# ESP32Design.net
KiCad netlist of a schematic drawn in Altium Designer
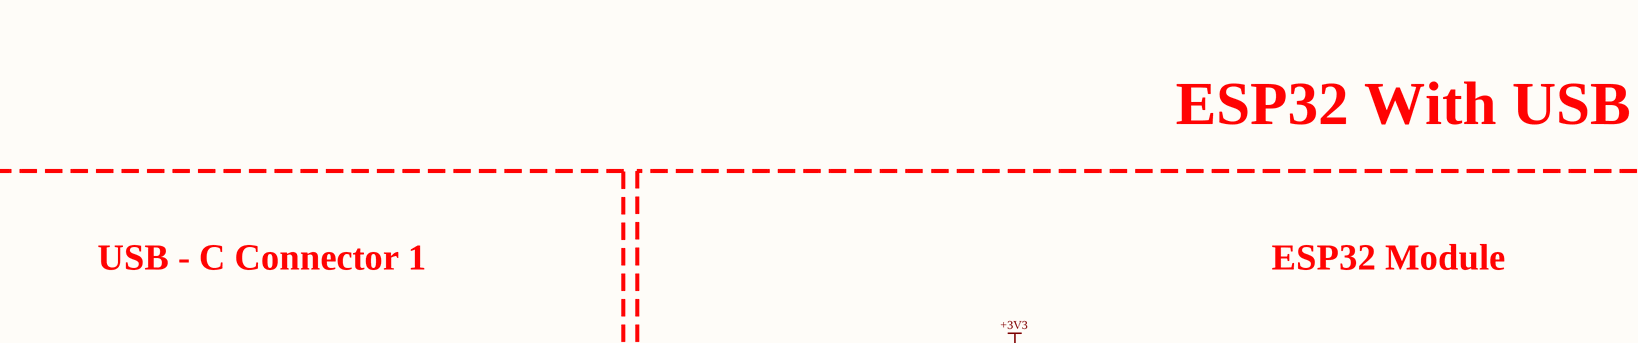
[diagram p0: ESP32Design.SchDoc, top left]
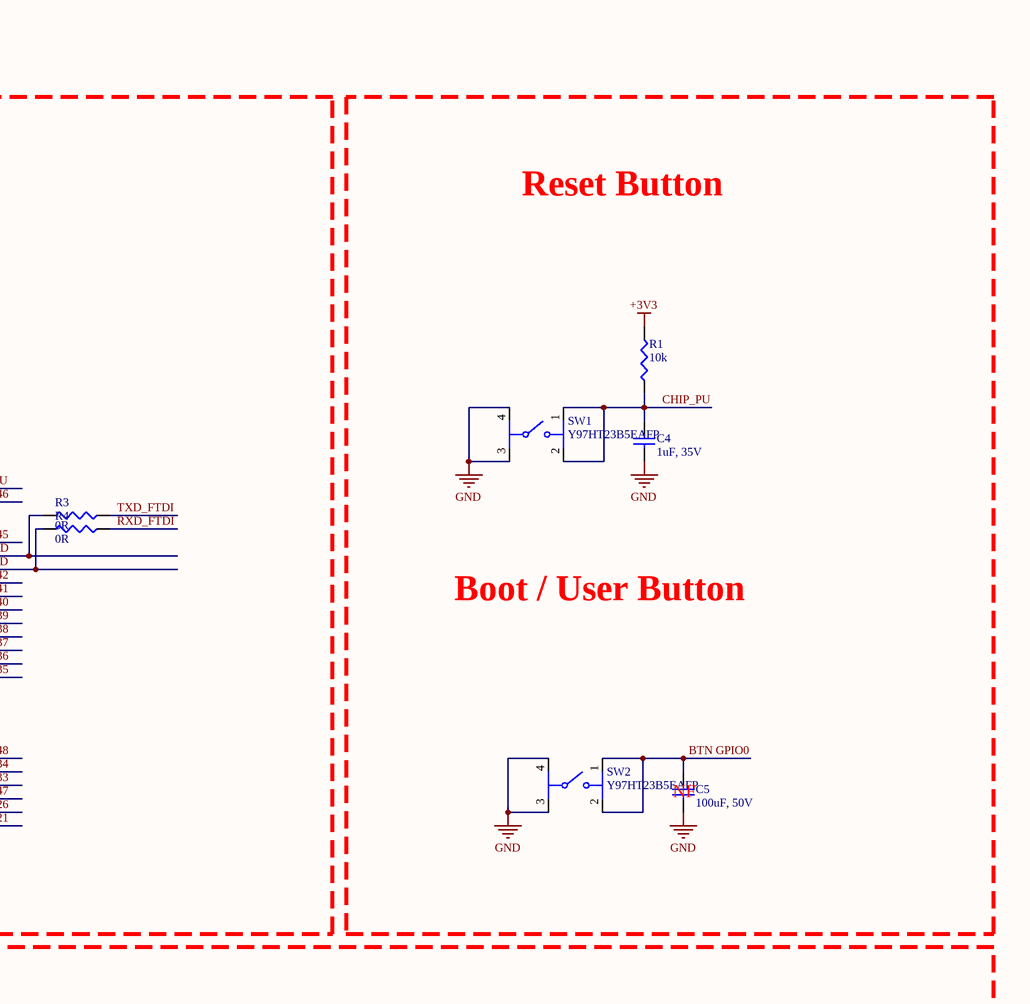
[diagram p1: ESP32Design.SchDoc, top right]
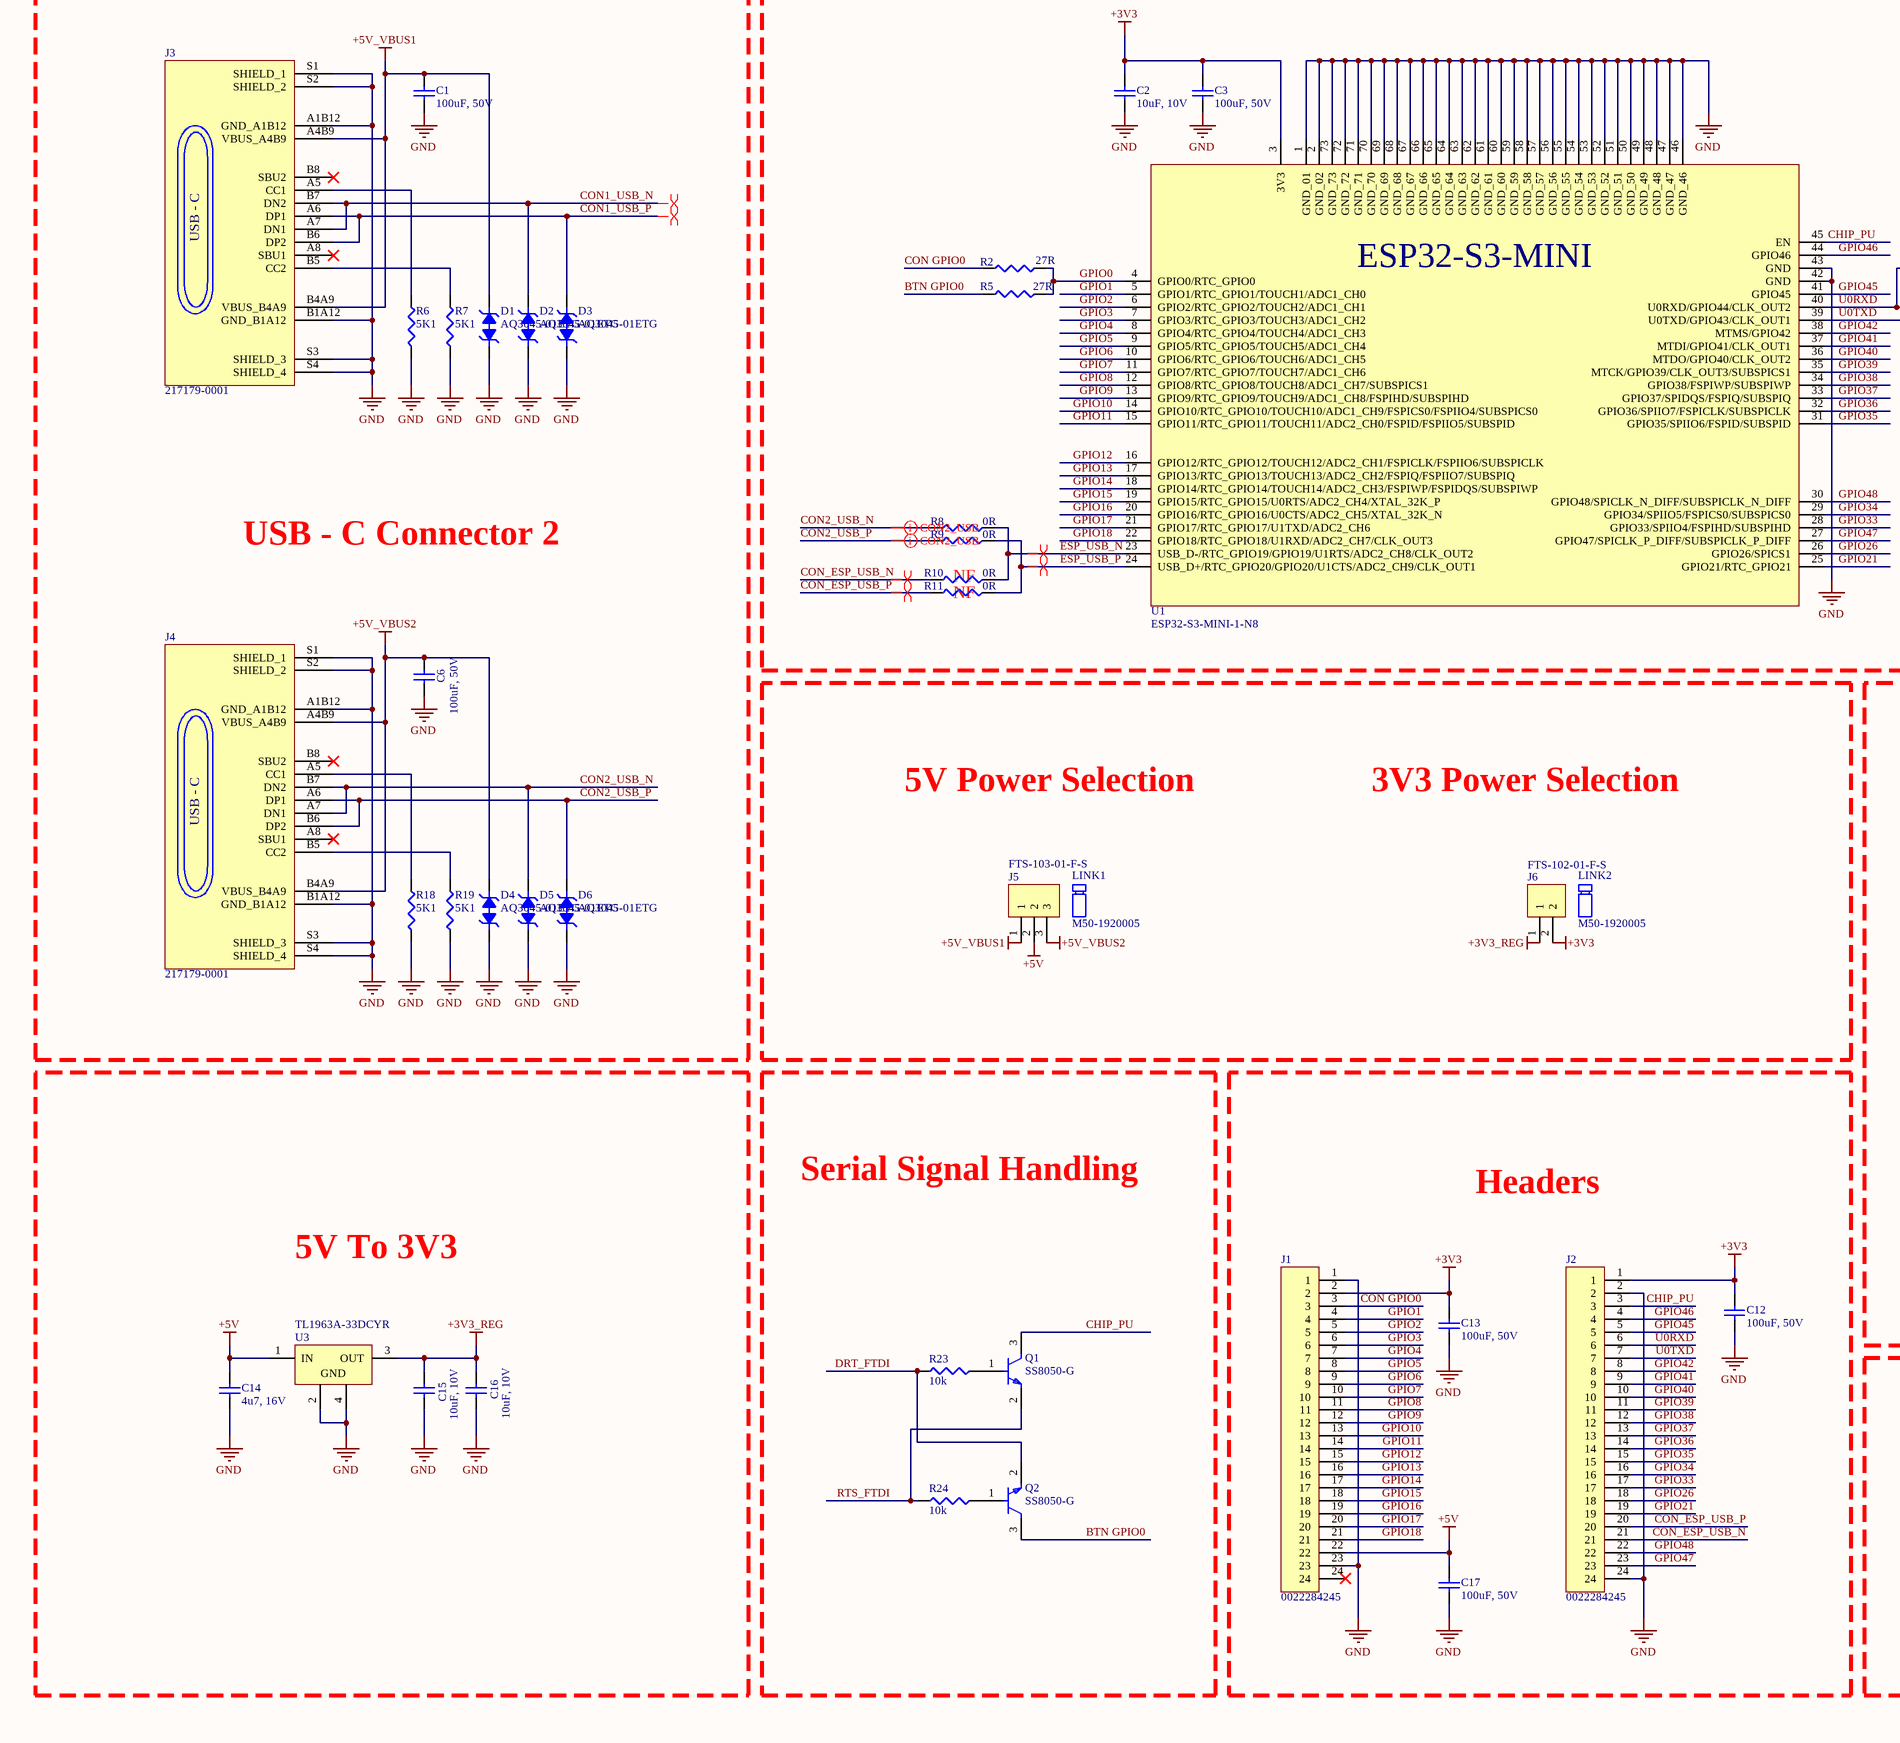
[diagram p2: ESP32Design.SchDoc, bottom left]
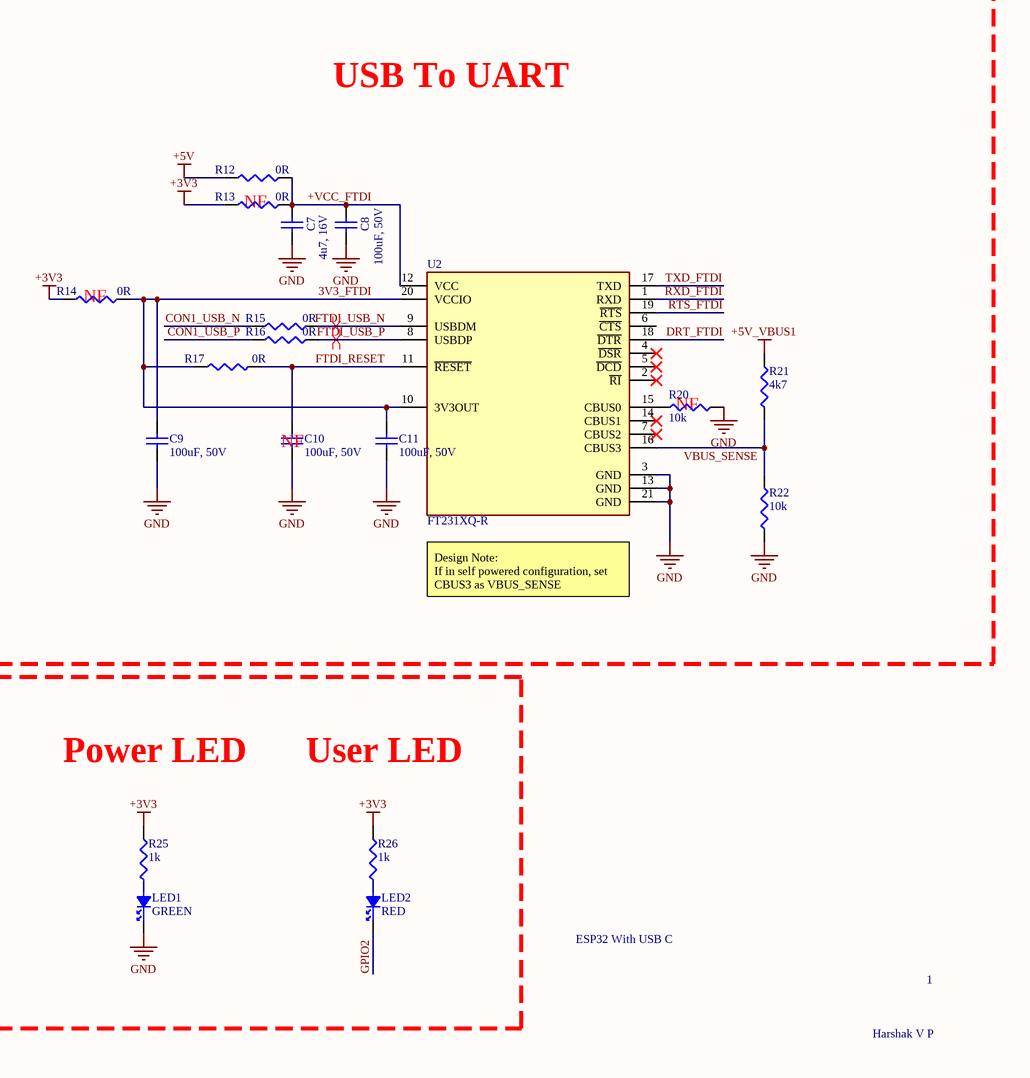
[diagram p3: ESP32Design.SchDoc, bottom right]

(export (version "E")
  (design (tool "Eeschema 10.0.6"))
  (components
    (comp (ref "C1")
      (value "100uF, 50V")
      (footprint "CAPC1005X65N")
      (description "CAP CER 0.1UF 50V X7R 0402")
      (fields
        (field (name "MANUFACTURER") "Samsung Electro-Mechanics")
        (field (name "MANUFACTURER PART NUMBER") "CL05B104KB54PNC")
      )
      (libsource (lib "SchLib") (part "CL05B104KB54PNC"))
    )
    (comp (ref "C2")
      (value "10uF, 10V")
      (footprint "CAPC1005X65N")
      (description "CAP CER 10UF 10V X5R 0402")
      (fields
        (field (name "MANUFACTURER") "Samsung Electro-Mechanics")
        (field (name "MANUFACTURER PART NUMBER") "CL05A106MP8NUB8")
      )
      (libsource (lib "SchLib") (part "CL05A106MP8NUB8"))
    )
    (comp (ref "C3")
      (value "100uF, 50V")
      (footprint "CAPC1005X65N")
      (description "CAP CER 0.1UF 50V X7R 0402")
      (fields
        (field (name "MANUFACTURER") "Samsung Electro-Mechanics")
        (field (name "MANUFACTURER PART NUMBER") "CL05B104KB54PNC")
      )
      (libsource (lib "SchLib") (part "CL05B104KB54PNC"))
    )
    (comp (ref "C4")
      (value "1uF, 35V")
      (footprint "CAPC1005X65N")
      (description "CAP CER 1UF 35V X5R 0402")
      (fields
        (field (name "MANUFACTURER") "Samsung Electro-Mechanics")
        (field (name "MANUFACTURER PART NUMBER") "CL05A105KL5NRNC")
      )
      (libsource (lib "SchLib") (part "CL05A105KL5NRNC"))
    )
    (comp (ref "C5")
      (value "100uF, 50V")
      (footprint "CAPC1005X65N")
      (description "CAP CER 0.1UF 50V X7R 0402")
      (fields
        (field (name "MANUFACTURER") "Samsung Electro-Mechanics")
        (field (name "MANUFACTURER PART NUMBER") "CL05B104KB54PNC")
      )
      (libsource (lib "SchLib") (part "CL05B104KB54PNC"))
    )
    (comp (ref "C6")
      (value "100uF, 50V")
      (footprint "CAPC1005X65N")
      (description "CAP CER 0.1UF 50V X7R 0402")
      (fields
        (field (name "MANUFACTURER") "Samsung Electro-Mechanics")
        (field (name "MANUFACTURER PART NUMBER") "CL05B104KB54PNC")
      )
      (libsource (lib "SchLib") (part "CL05B104KB54PNC"))
    )
    (comp (ref "C7")
      (value "4u7, 16V")
      (footprint "CAPC1005X65N")
      (description "CAP CER 4.7UF 16V X5R 0402")
      (fields
        (field (name "MANUFACTURER") "Samsung Electro-Mechanics")
        (field (name "MANUFACTURER PART NUMBER") "CL05A475MO5NUNC")
      )
      (libsource (lib "SchLib") (part "CL05A475MO5NUNC"))
    )
    (comp (ref "C8")
      (value "100uF, 50V")
      (footprint "CAPC1005X65N")
      (description "CAP CER 0.1UF 50V X7R 0402")
      (fields
        (field (name "MANUFACTURER") "Samsung Electro-Mechanics")
        (field (name "MANUFACTURER PART NUMBER") "CL05B104KB54PNC")
      )
      (libsource (lib "SchLib") (part "CL05B104KB54PNC"))
    )
    (comp (ref "C9")
      (value "100uF, 50V")
      (footprint "CAPC1005X65N")
      (description "CAP CER 0.1UF 50V X7R 0402")
      (fields
        (field (name "MANUFACTURER") "Samsung Electro-Mechanics")
        (field (name "MANUFACTURER PART NUMBER") "CL05B104KB54PNC")
      )
      (libsource (lib "SchLib") (part "CL05B104KB54PNC"))
    )
    (comp (ref "C10")
      (value "100uF, 50V")
      (footprint "CAPC1005X65N")
      (description "CAP CER 0.1UF 50V X7R 0402")
      (fields
        (field (name "MANUFACTURER") "Samsung Electro-Mechanics")
        (field (name "MANUFACTURER PART NUMBER") "CL05B104KB54PNC")
      )
      (libsource (lib "SchLib") (part "CL05B104KB54PNC"))
    )
    (comp (ref "C11")
      (value "100uF, 50V")
      (footprint "CAPC1005X65N")
      (description "CAP CER 0.1UF 50V X7R 0402")
      (fields
        (field (name "MANUFACTURER") "Samsung Electro-Mechanics")
        (field (name "MANUFACTURER PART NUMBER") "CL05B104KB54PNC")
      )
      (libsource (lib "SchLib") (part "CL05B104KB54PNC"))
    )
    (comp (ref "C12")
      (value "100uF, 50V")
      (footprint "CAPC1005X65N")
      (description "CAP CER 0.1UF 50V X7R 0402")
      (fields
        (field (name "MANUFACTURER") "Samsung Electro-Mechanics")
        (field (name "MANUFACTURER PART NUMBER") "CL05B104KB54PNC")
      )
      (libsource (lib "SchLib") (part "CL05B104KB54PNC"))
    )
    (comp (ref "C13")
      (value "100uF, 50V")
      (footprint "CAPC1005X65N")
      (description "CAP CER 0.1UF 50V X7R 0402")
      (fields
        (field (name "MANUFACTURER") "Samsung Electro-Mechanics")
        (field (name "MANUFACTURER PART NUMBER") "CL05B104KB54PNC")
      )
      (libsource (lib "SchLib") (part "CL05B104KB54PNC"))
    )
    (comp (ref "C14")
      (value "4u7, 16V")
      (footprint "CAPC1005X65N")
      (description "CAP CER 4.7UF 16V X5R 0402")
      (fields
        (field (name "MANUFACTURER") "Samsung Electro-Mechanics")
        (field (name "MANUFACTURER PART NUMBER") "CL05A475MO5NUNC")
      )
      (libsource (lib "SchLib") (part "CL05A475MO5NUNC"))
    )
    (comp (ref "C15")
      (value "10uF, 10V")
      (footprint "CAPC1005X65N")
      (description "CAP CER 10UF 10V X5R 0402")
      (fields
        (field (name "MANUFACTURER") "Samsung Electro-Mechanics")
        (field (name "MANUFACTURER PART NUMBER") "CL05A106MP8NUB8")
      )
      (libsource (lib "SchLib") (part "CL05A106MP8NUB8"))
    )
    (comp (ref "C16")
      (value "10uF, 10V")
      (footprint "CAPC1005X65N")
      (description "CAP CER 10UF 10V X5R 0402")
      (fields
        (field (name "MANUFACTURER") "Samsung Electro-Mechanics")
        (field (name "MANUFACTURER PART NUMBER") "CL05A106MP8NUB8")
      )
      (libsource (lib "SchLib") (part "CL05A106MP8NUB8"))
    )
    (comp (ref "C17")
      (value "100uF, 50V")
      (footprint "CAPC1005X65N")
      (description "CAP CER 0.1UF 50V X7R 0402")
      (fields
        (field (name "MANUFACTURER") "Samsung Electro-Mechanics")
        (field (name "MANUFACTURER PART NUMBER") "CL05B104KB54PNC")
      )
      (libsource (lib "SchLib") (part "CL05B104KB54PNC"))
    )
    (comp (ref "D1")
      (value "AQ3045-01ETG")
      (footprint "SOD882")
      (description "TVS DIODE 5.3VWM 12VC SOD882")
      (fields (field (name "MANUFACTURER") "Littelfuse") (field (name "LCS PART NUMBER") "C3710326"))
      (libsource (lib "SchLib") (part "AQ3045-01ETG"))
    )
    (comp (ref "D2")
      (value "AQ3045-01ETG")
      (footprint "SOD882")
      (description "TVS DIODE 5.3VWM 12VC SOD882")
      (fields (field (name "MANUFACTURER") "Littelfuse") (field (name "LCS PART NUMBER") "C3710326"))
      (libsource (lib "SchLib") (part "AQ3045-01ETG"))
    )
    (comp (ref "D3")
      (value "AQ3045-01ETG")
      (footprint "SOD882")
      (description "TVS DIODE 5.3VWM 12VC SOD882")
      (fields (field (name "MANUFACTURER") "Littelfuse") (field (name "LCS PART NUMBER") "C3710326"))
      (libsource (lib "SchLib") (part "AQ3045-01ETG"))
    )
    (comp (ref "D4")
      (value "AQ3045-01ETG")
      (footprint "SOD882")
      (description "TVS DIODE 5.3VWM 12VC SOD882")
      (fields (field (name "MANUFACTURER") "Littelfuse") (field (name "LCS PART NUMBER") "C3710326"))
      (libsource (lib "SchLib") (part "AQ3045-01ETG"))
    )
    (comp (ref "D5")
      (value "AQ3045-01ETG")
      (footprint "SOD882")
      (description "TVS DIODE 5.3VWM 12VC SOD882")
      (fields (field (name "MANUFACTURER") "Littelfuse") (field (name "LCS PART NUMBER") "C3710326"))
      (libsource (lib "SchLib") (part "AQ3045-01ETG"))
    )
    (comp (ref "D6")
      (value "AQ3045-01ETG")
      (footprint "SOD882")
      (description "TVS DIODE 5.3VWM 12VC SOD882")
      (fields (field (name "MANUFACTURER") "Littelfuse") (field (name "LCS PART NUMBER") "C3710326"))
      (libsource (lib "SchLib") (part "AQ3045-01ETG"))
    )
    (comp (ref "J1")
      (value "0022284245")
      (footprint "HDR_1X24_2.54MM")
      (description "CONN HEADER VERT 24POS 2.54MM")
      (fields (field (name "MANUFACTURER") "Molex") (field (name "MANUFACTURER PART NUMBER") "22-28-4245"))
      (libsource (lib "SchLib") (part "0022284245"))
    )
    (comp (ref "J2")
      (value "0022284245")
      (footprint "HDR_1X24_2.54MM")
      (description "CONN HEADER VERT 24POS 2.54MM")
      (fields (field (name "MANUFACTURER") "Molex") (field (name "MANUFACTURER PART NUMBER") "22-28-4245"))
      (libsource (lib "SchLib") (part "0022284245"))
    )
    (comp (ref "J3")
      (value "217179-0001")
      (footprint "FP-2171790001-MFG")
      (description "CONN RCP USB2.0 TYP C 24P SMD RA")
      (fields (field (name "MANUFACTURER") "Molex") (field (name "LCSC PART NUMBER") "C3197684"))
      (libsource (lib "SchLib") (part "217179-0001"))
    )
    (comp (ref "J4")
      (value "217179-0001")
      (footprint "FP-2171790001-MFG")
      (description "CONN RCP USB2.0 TYP C 24P SMD RA")
      (fields (field (name "MANUFACTURER") "Molex") (field (name "LCSC PART NUMBER") "C3197684"))
      (libsource (lib "SchLib") (part "217179-0001"))
    )
    (comp (ref "J5")
      (value "FTS-103-01-F-S")
      (footprint "HDR_1X3_1.27MM")
      (description "CONN HEADER VERT 3POS 1.27MM")
      (fields (field (name "MANUFACTURER") "Samtec") (field (name "LCSC PART NUMBER") "C3333578"))
      (libsource (lib "SchLib") (part "FTS-103-01-F-S"))
    )
    (comp (ref "J6")
      (value "FTS-102-01-F-S")
      (footprint "HDR_1X2_1.27MM")
      (description "CONN HEADER VERT 2POS 1.27MM")
      (fields (field (name "MANUFACTURER") "Samtec"))
      (libsource (lib "SchLib") (part "FTS-102-01-F-S"))
    )
    (comp (ref "LED1")
      (value "GREEN")
      (footprint "LED0402G")
      (description "LED GREEN 0402 SMD")
      (fields
        (field (name "MANUFACTURER") "Vishay")
        (field (name "MANUFACTURER PART NUMBER") "VLMTG1500-GS08")
      )
      (libsource (lib "SchLib") (part "VLMTG1500-GS08"))
    )
    (comp (ref "LED2")
      (value "RED")
      (footprint "LED0402R")
      (description "CHIPLED(0402) SUPER RED ULTRABRI")
      (fields
        (field (name "MANUFACTURER") "Vishay")
        (field (name "MANUFACTURER PART NUMBER") "VLMS1502-GS08")
      )
      (libsource (lib "SchLib") (part "VLMS1502-GS08"))
    )
    (comp (ref "LINK1")
      (value "M50-1920005")
      (description "CONN SHUNT 1.27MM RED")
      (fields (field (name "MANUFACTURER") "Harwin"))
      (libsource (lib "SchLib") (part "M50-1920005"))
    )
    (comp (ref "LINK2")
      (value "M50-1920005")
      (description "CONN SHUNT 1.27MM RED")
      (fields (field (name "MANUFACTURER") "Harwin"))
      (libsource (lib "SchLib") (part "M50-1920005"))
    )
    (comp (ref "Q1")
      (value "SS8050-G")
      (footprint "FP-SS8050-G-IPC_B")
      (description "TRANS NPN 25V 1.5A SOT-23-3")
      (fields (field (name "MANUFACTURER") "Comchip"))
      (libsource (lib "SchLib") (part "SS8050-G"))
    )
    (comp (ref "Q2")
      (value "SS8050-G")
      (footprint "FP-SS8050-G-IPC_B")
      (description "TRANS NPN 25V 1.5A SOT-23-3")
      (fields (field (name "MANUFACTURER") "Comchip"))
      (libsource (lib "SchLib") (part "SS8050-G"))
    )
    (comp (ref "R1")
      (value "10k")
      (footprint "RESC1005X37N")
      (description "RES SMD 10K OHM 1% 1/16W 0402")
      (fields
        (field (name "MANUFACTURER") "Yageo Group")
        (field (name "MANUFACTURER PART NUMBER") "AC0402FR-0710KL")
      )
      (libsource (lib "SchLib") (part "AC0402FR-0710KL"))
    )
    (comp (ref "R2")
      (value "27R")
      (footprint "RESC1005X37N")
      (description "RES 27 OHM 1% 1/16W 0402")
      (fields
        (field (name "MANUFACTURER") "Yageo Group")
        (field (name "MANUFACTURER PART NUMBER") "RC0402FR-0727RL")
      )
      (libsource (lib "SchLib") (part "RC0402FR-0727RL"))
    )
    (comp (ref "R3")
      (value "0R")
      (footprint "RESC1005X37N")
      (description "RES 0 OHM JUMPER 1/16W 0402")
      (fields
        (field (name "MANUFACTURER") "Yageo Group")
        (field (name "MANUFACTURER PART NUMBER") "RC0402JR-070RL")
      )
      (libsource (lib "SchLib") (part "RC0402JR-070RL"))
    )
    (comp (ref "R4")
      (value "0R")
      (footprint "RESC1005X37N")
      (description "RES 0 OHM JUMPER 1/16W 0402")
      (fields
        (field (name "MANUFACTURER") "Yageo Group")
        (field (name "MANUFACTURER PART NUMBER") "RC0402JR-070RL")
      )
      (libsource (lib "SchLib") (part "RC0402JR-070RL"))
    )
    (comp (ref "R5")
      (value "27R")
      (footprint "RESC1005X37N")
      (description "RES 27 OHM 1% 1/16W 0402")
      (fields
        (field (name "MANUFACTURER") "Yageo Group")
        (field (name "MANUFACTURER PART NUMBER") "RC0402FR-0727RL")
      )
      (libsource (lib "SchLib") (part "RC0402FR-0727RL"))
    )
    (comp (ref "R6")
      (value "5K1")
      (footprint "RESC1005X37N")
      (description "RES SMD 5.1K OHM 1% 1/16W 0402")
      (fields
        (field (name "MANUFACTURER") "Yageo Group")
        (field (name "MANUFACTURER PART NUMBER") "AC0402FR-075K1L")
      )
      (libsource (lib "SchLib") (part "AC0402FR-075K1L"))
    )
    (comp (ref "R7")
      (value "5K1")
      (footprint "RESC1005X37N")
      (description "RES SMD 5.1K OHM 1% 1/16W 0402")
      (fields
        (field (name "MANUFACTURER") "Yageo Group")
        (field (name "MANUFACTURER PART NUMBER") "AC0402FR-075K1L")
      )
      (libsource (lib "SchLib") (part "AC0402FR-075K1L"))
    )
    (comp (ref "R8")
      (value "0R")
      (footprint "RESC1005X37N")
      (description "RES 0 OHM JUMPER 1/16W 0402")
      (fields
        (field (name "MANUFACTURER") "Yageo Group")
        (field (name "MANUFACTURER PART NUMBER") "RC0402JR-070RL")
      )
      (libsource (lib "SchLib") (part "RC0402JR-070RL"))
    )
    (comp (ref "R9")
      (value "0R")
      (footprint "RESC1005X37N")
      (description "RES 0 OHM JUMPER 1/16W 0402")
      (fields
        (field (name "MANUFACTURER") "Yageo Group")
        (field (name "MANUFACTURER PART NUMBER") "RC0402JR-070RL")
      )
      (libsource (lib "SchLib") (part "RC0402JR-070RL"))
    )
    (comp (ref "R10")
      (value "0R")
      (footprint "RESC1005X37N")
      (description "RES 0 OHM JUMPER 1/16W 0402")
      (fields
        (field (name "MANUFACTURER") "Yageo Group")
        (field (name "MANUFACTURER PART NUMBER") "RC0402JR-070RL")
      )
      (libsource (lib "SchLib") (part "RC0402JR-070RL"))
    )
    (comp (ref "R11")
      (value "0R")
      (footprint "RESC1005X37N")
      (description "RES 0 OHM JUMPER 1/16W 0402")
      (fields
        (field (name "MANUFACTURER") "Yageo Group")
        (field (name "MANUFACTURER PART NUMBER") "RC0402JR-070RL")
      )
      (libsource (lib "SchLib") (part "RC0402JR-070RL"))
    )
    (comp (ref "R12")
      (value "0R")
      (footprint "RESC1005X37N")
      (description "RES 0 OHM JUMPER 1/16W 0402")
      (fields
        (field (name "MANUFACTURER") "Yageo Group")
        (field (name "MANUFACTURER PART NUMBER") "RC0402JR-070RL")
      )
      (libsource (lib "SchLib") (part "RC0402JR-070RL"))
    )
    (comp (ref "R13")
      (value "0R")
      (footprint "RESC1005X37N")
      (description "RES 0 OHM JUMPER 1/16W 0402")
      (fields
        (field (name "MANUFACTURER") "Yageo Group")
        (field (name "MANUFACTURER PART NUMBER") "RC0402JR-070RL")
      )
      (libsource (lib "SchLib") (part "RC0402JR-070RL"))
    )
    (comp (ref "R14")
      (value "0R")
      (footprint "RESC1005X37N")
      (description "RES 0 OHM JUMPER 1/16W 0402")
      (fields
        (field (name "MANUFACTURER") "Yageo Group")
        (field (name "MANUFACTURER PART NUMBER") "RC0402JR-070RL")
      )
      (libsource (lib "SchLib") (part "RC0402JR-070RL"))
    )
    (comp (ref "R15")
      (value "0R")
      (footprint "RESC1005X37N")
      (description "RES 0 OHM JUMPER 1/16W 0402")
      (fields
        (field (name "MANUFACTURER") "Yageo Group")
        (field (name "MANUFACTURER PART NUMBER") "RC0402JR-070RL")
      )
      (libsource (lib "SchLib") (part "RC0402JR-070RL"))
    )
    (comp (ref "R16")
      (value "0R")
      (footprint "RESC1005X37N")
      (description "RES 0 OHM JUMPER 1/16W 0402")
      (fields
        (field (name "MANUFACTURER") "Yageo Group")
        (field (name "MANUFACTURER PART NUMBER") "RC0402JR-070RL")
      )
      (libsource (lib "SchLib") (part "RC0402JR-070RL"))
    )
    (comp (ref "R17")
      (value "0R")
      (footprint "RESC1005X37N")
      (description "RES 0 OHM JUMPER 1/16W 0402")
      (fields
        (field (name "MANUFACTURER") "Yageo Group")
        (field (name "MANUFACTURER PART NUMBER") "RC0402JR-070RL")
      )
      (libsource (lib "SchLib") (part "RC0402JR-070RL"))
    )
    (comp (ref "R18")
      (value "5K1")
      (footprint "RESC1005X37N")
      (description "RES SMD 5.1K OHM 1% 1/16W 0402")
      (fields
        (field (name "MANUFACTURER") "Yageo Group")
        (field (name "MANUFACTURER PART NUMBER") "AC0402FR-075K1L")
      )
      (libsource (lib "SchLib") (part "AC0402FR-075K1L"))
    )
    (comp (ref "R19")
      (value "5K1")
      (footprint "RESC1005X37N")
      (description "RES SMD 5.1K OHM 1% 1/16W 0402")
      (fields
        (field (name "MANUFACTURER") "Yageo Group")
        (field (name "MANUFACTURER PART NUMBER") "AC0402FR-075K1L")
      )
      (libsource (lib "SchLib") (part "AC0402FR-075K1L"))
    )
    (comp (ref "R20")
      (value "10k")
      (footprint "RESC1005X37N")
      (description "RES SMD 10K OHM 1% 1/16W 0402")
      (fields
        (field (name "MANUFACTURER") "Yageo Group")
        (field (name "MANUFACTURER PART NUMBER") "AC0402FR-0710KL")
      )
      (libsource (lib "SchLib") (part "AC0402FR-0710KL"))
    )
    (comp (ref "R21")
      (value "4k7")
      (footprint "RESC1005X37N")
      (description "RES SMD 4.7K OHM 0.1% 1/16W 0402")
      (fields
        (field (name "MANUFACTURER") "Yageo Group")
        (field (name "MANUFACTURER PART NUMBER") "RT0402BRB074K7L")
      )
      (libsource (lib "SchLib") (part "RT0402BRB074K7L"))
    )
    (comp (ref "R22")
      (value "10k")
      (footprint "RESC1005X37N")
      (description "RES SMD 10K OHM 1% 1/16W 0402")
      (fields
        (field (name "MANUFACTURER") "Yageo Group")
        (field (name "MANUFACTURER PART NUMBER") "AC0402FR-0710KL")
      )
      (libsource (lib "SchLib") (part "AC0402FR-0710KL"))
    )
    (comp (ref "R23")
      (value "10k")
      (footprint "RESC1005X37N")
      (description "RES SMD 10K OHM 1% 1/16W 0402")
      (fields
        (field (name "MANUFACTURER") "Yageo Group")
        (field (name "MANUFACTURER PART NUMBER") "AC0402FR-0710KL")
      )
      (libsource (lib "SchLib") (part "AC0402FR-0710KL"))
    )
    (comp (ref "R24")
      (value "10k")
      (footprint "RESC1005X37N")
      (description "RES SMD 10K OHM 1% 1/16W 0402")
      (fields
        (field (name "MANUFACTURER") "Yageo Group")
        (field (name "MANUFACTURER PART NUMBER") "AC0402FR-0710KL")
      )
      (libsource (lib "SchLib") (part "AC0402FR-0710KL"))
    )
    (comp (ref "R25")
      (value "1k")
      (footprint "RESC1005X37N")
      (description "RES 1K OHM 1% 1/16W 0402")
      (fields
        (field (name "MANUFACTURER") "Yageo Group")
        (field (name "MANUFACTURER PART NUMBER") "RC0402FR-071KL")
      )
      (libsource (lib "SchLib") (part "RC0402FR-071KL"))
    )
    (comp (ref "R26")
      (value "1k")
      (footprint "RESC1005X37N")
      (description "RES 1K OHM 1% 1/16W 0402")
      (fields
        (field (name "MANUFACTURER") "Yageo Group")
        (field (name "MANUFACTURER PART NUMBER") "RC0402FR-071KL")
      )
      (libsource (lib "SchLib") (part "RC0402FR-071KL"))
    )
    (comp (ref "SW1")
      (value "Y97HT23B5EAFP")
      (footprint "SWITCH_45SK43SMTR92LFS")
      (description "SWITCH TACTILE SPST-NO 0.05A 12V")
      (fields (field (name "MANUFACTURER") "C&K Components") (field (name "LCSC PART NUMBER") "C20773526"))
      (libsource (lib "SchLib") (part "Y97HT23B5EAFP"))
    )
    (comp (ref "SW2")
      (value "Y97HT23B5EAFP")
      (footprint "SWITCH_45SK43SMTR92LFS")
      (description "SWITCH TACTILE SPST-NO 0.05A 12V")
      (fields (field (name "MANUFACTURER") "C&K Components") (field (name "LCSC PART NUMBER") "C20773526"))
      (libsource (lib "SchLib") (part "Y97HT23B5EAFP"))
    )
    (comp (ref "U1")
      (value "ESP32-S3-MINI-1-N8")
      (footprint "XCVR_ESP32-S3-MINI-1-N8")
      (description "20.5dBm ESP32-S3FN8 Chip 2.4GHz SMD WiFi Modules ROHS")
      (fields (field (name "MANUFACTURER") "Espressif Systems") (field (name "LCSC PART NUMBER") "C2913206"))
      (libsource (lib "SchLib") (part "ESP32-S3-MINI-1-N8"))
    )
    (comp (ref "U2")
      (value "FT231XQ-R")
      (footprint "FP-QFN-20-IPC_B")
      (description "IC USB SERIAL FULL UART 20QFN")
      (fields (field (name "MANUFACTURER") "FTDI") (field (name "LCSC PART NUMBER") "C132159"))
      (libsource (lib "SchLib") (part "FT231XQ-R"))
    )
    (comp (ref "U3")
      (value "TL1963A-33DCYR")
      (footprint "DCY0004A_N")
      (description "IC REG LIN 3.3V 1.5A SOT-223-4")
      (fields (field (name "MANUFACTURER") "Texas Instruments") (field (name "LCSC PART NUMBER") "C181262"))
      (libsource (lib "SchLib") (part "TL1963A-33DCYR"))
    )
  )
  (nets
    (net (code "1") (name "+3V3") (class "Default")
      (node (ref "C12") (pin "2") (pinfunction "2_2") (pintype "passive"))
      (node (ref "C13") (pin "2") (pinfunction "2_2") (pintype "passive"))
      (node (ref "C2") (pin "2") (pinfunction "2_2") (pintype "passive"))
      (node (ref "C3") (pin "2") (pinfunction "2_2") (pintype "passive"))
      (node (ref "J1") (pin "2") (pinfunction "2_2") (pintype "passive"))
      (node (ref "J2") (pin "1") (pinfunction "1_1") (pintype "passive"))
      (node (ref "J6") (pin "2") (pinfunction "2_2") (pintype "passive"))
      (node (ref "R1") (pin "2") (pinfunction "2_2") (pintype "passive"))
      (node (ref "R13") (pin "1") (pinfunction "1_1") (pintype "passive"))
      (node (ref "R14") (pin "1") (pinfunction "1_1") (pintype "passive"))
      (node (ref "R25") (pin "2") (pinfunction "2_2") (pintype "passive"))
      (node (ref "R26") (pin "2") (pinfunction "2_2") (pintype "passive"))
      (node (ref "U1") (pin "3") (pinfunction "3V3_3") (pintype "passive"))
    )
    (net (code "2") (name "+3V3_REG") (class "Default")
      (node (ref "C15") (pin "2") (pinfunction "2_2") (pintype "passive"))
      (node (ref "C16") (pin "2") (pinfunction "2_2") (pintype "passive"))
      (node (ref "J6") (pin "1") (pinfunction "1_1") (pintype "passive"))
      (node (ref "U3") (pin "3") (pinfunction "OUT_3") (pintype "power_in"))
    )
    (net (code "3") (name "+5V") (class "Default")
      (node (ref "C14") (pin "2") (pinfunction "2_2") (pintype "passive"))
      (node (ref "C17") (pin "2") (pinfunction "2_2") (pintype "passive"))
      (node (ref "J1") (pin "22") (pinfunction "22_22") (pintype "passive"))
      (node (ref "J5") (pin "2") (pinfunction "2_2") (pintype "passive"))
      (node (ref "R12") (pin "1") (pinfunction "1_1") (pintype "passive"))
      (node (ref "U3") (pin "1") (pinfunction "IN_1") (pintype "power_in"))
    )
    (net (code "4") (name "+5V_VBUS1") (class "Default")
      (node (ref "C1") (pin "2") (pinfunction "2_2") (pintype "passive"))
      (node (ref "D1") (pin "2") (pinfunction "2_2") (pintype "passive"))
      (node (ref "J3") (pin "A4B9") (pinfunction "VBUS_A4B9_A4B9") (pintype "passive"))
      (node (ref "J3") (pin "B4A9") (pinfunction "VBUS_B4A9_B4A9") (pintype "passive"))
      (node (ref "J5") (pin "1") (pinfunction "1_1") (pintype "passive"))
      (node (ref "R21") (pin "2") (pinfunction "2_2") (pintype "passive"))
    )
    (net (code "5") (name "+5V_VBUS2") (class "Default")
      (node (ref "C6") (pin "2") (pinfunction "2_2") (pintype "passive"))
      (node (ref "D4") (pin "2") (pinfunction "2_2") (pintype "passive"))
      (node (ref "J4") (pin "A4B9") (pinfunction "VBUS_A4B9_A4B9") (pintype "passive"))
      (node (ref "J4") (pin "B4A9") (pinfunction "VBUS_B4A9_B4A9") (pintype "passive"))
      (node (ref "J5") (pin "3") (pinfunction "3_3") (pintype "passive"))
    )
    (net (code "6") (name "/+VCC_FTDI") (class "Default")
      (node (ref "C7") (pin "2") (pinfunction "2_2") (pintype "passive"))
      (node (ref "C8") (pin "2") (pinfunction "2_2") (pintype "passive"))
      (node (ref "R12") (pin "2") (pinfunction "2_2") (pintype "passive"))
      (node (ref "R13") (pin "2") (pinfunction "2_2") (pintype "passive"))
      (node (ref "U2") (pin "12") (pinfunction "VCC_12") (pintype "passive"))
    )
    (net (code "7") (name "/3V3_FTDI") (class "Default")
      (node (ref "C11") (pin "2") (pinfunction "2_2") (pintype "passive"))
      (node (ref "C9") (pin "2") (pinfunction "2_2") (pintype "passive"))
      (node (ref "R14") (pin "2") (pinfunction "2_2") (pintype "passive"))
      (node (ref "R17") (pin "1") (pinfunction "1_1") (pintype "passive"))
      (node (ref "U2") (pin "10") (pinfunction "3V3OUT_10") (pintype "passive"))
      (node (ref "U2") (pin "20") (pinfunction "VCCIO_20") (pintype "passive"))
    )
    (net (code "8") (name "/BTN GPIO0") (class "Default")
      (node (ref "C5") (pin "2") (pinfunction "2_2") (pintype "passive"))
      (node (ref "Q2") (pin "3") (pinfunction "C_3") (pintype "passive"))
      (node (ref "R5") (pin "1") (pinfunction "1_1") (pintype "passive"))
      (node (ref "SW2") (pin "1") (pinfunction "1_1") (pintype "passive"))
      (node (ref "SW2") (pin "2") (pinfunction "2_2") (pintype "passive"))
    )
    (net (code "9") (name "/CHIP_PU") (class "Default")
      (node (ref "C4") (pin "2") (pinfunction "2_2") (pintype "passive"))
      (node (ref "J2") (pin "3") (pinfunction "3_3") (pintype "passive"))
      (node (ref "Q1") (pin "3") (pinfunction "C_3") (pintype "passive"))
      (node (ref "R1") (pin "1") (pinfunction "1_1") (pintype "passive"))
      (node (ref "SW1") (pin "1") (pinfunction "1_1") (pintype "passive"))
      (node (ref "SW1") (pin "2") (pinfunction "2_2") (pintype "passive"))
      (node (ref "U1") (pin "45") (pinfunction "EN_45") (pintype "passive"))
    )
    (net (code "10") (name "/CON GPIO0") (class "Default")
      (node (ref "J1") (pin "3") (pinfunction "3_3") (pintype "passive"))
      (node (ref "R2") (pin "1") (pinfunction "1_1") (pintype "passive"))
    )
    (net (code "11") (name "/CON1_USB_N") (class "Default")
      (node (ref "D2") (pin "2") (pinfunction "2_2") (pintype "passive"))
      (node (ref "J3") (pin "A7") (pinfunction "DN1_A7") (pintype "passive"))
      (node (ref "J3") (pin "B7") (pinfunction "DN2_B7") (pintype "passive"))
      (node (ref "R15") (pin "1") (pinfunction "1_1") (pintype "passive"))
    )
    (net (code "12") (name "/CON1_USB_P") (class "Default")
      (node (ref "D3") (pin "2") (pinfunction "2_2") (pintype "passive"))
      (node (ref "J3") (pin "A6") (pinfunction "DP1_A6") (pintype "passive"))
      (node (ref "J3") (pin "B6") (pinfunction "DP2_B6") (pintype "passive"))
      (node (ref "R16") (pin "1") (pinfunction "1_1") (pintype "passive"))
    )
    (net (code "13") (name "/CON2_USB_N") (class "Default")
      (node (ref "D5") (pin "2") (pinfunction "2_2") (pintype "passive"))
      (node (ref "J4") (pin "A7") (pinfunction "DN1_A7") (pintype "passive"))
      (node (ref "J4") (pin "B7") (pinfunction "DN2_B7") (pintype "passive"))
      (node (ref "R8") (pin "1") (pinfunction "1_1") (pintype "passive"))
    )
    (net (code "14") (name "/CON2_USB_P") (class "Default")
      (node (ref "D6") (pin "2") (pinfunction "2_2") (pintype "passive"))
      (node (ref "J4") (pin "A6") (pinfunction "DP1_A6") (pintype "passive"))
      (node (ref "J4") (pin "B6") (pinfunction "DP2_B6") (pintype "passive"))
      (node (ref "R9") (pin "1") (pinfunction "1_1") (pintype "passive"))
    )
    (net (code "15") (name "/CON_ESP_USB_N") (class "Default")
      (node (ref "J2") (pin "21") (pinfunction "21_21") (pintype "passive"))
      (node (ref "R10") (pin "1") (pinfunction "1_1") (pintype "passive"))
    )
    (net (code "16") (name "/CON_ESP_USB_P") (class "Default")
      (node (ref "J2") (pin "20") (pinfunction "20_20") (pintype "passive"))
      (node (ref "R11") (pin "1") (pinfunction "1_1") (pintype "passive"))
    )
    (net (code "17") (name "/DRT_FTDI") (class "Default")
      (node (ref "Q2") (pin "2") (pinfunction "E_2") (pintype "passive"))
      (node (ref "R23") (pin "1") (pinfunction "1_1") (pintype "passive"))
      (node (ref "U2") (pin "18") (pinfunction "~{DTR}_18") (pintype "passive"))
    )
    (net (code "18") (name "/ESP_USB_N") (class "Default")
      (node (ref "R10") (pin "2") (pinfunction "2_2") (pintype "passive"))
      (node (ref "R8") (pin "2") (pinfunction "2_2") (pintype "passive"))
      (node (ref "U1") (pin "23") (pinfunction "USB_D-/RTC_GPIO19/GPIO19/U1RTS/ADC2_CH8/CLK_OUT2_23") (pintype "passive"))
    )
    (net (code "19") (name "/ESP_USB_P") (class "Default")
      (node (ref "R11") (pin "2") (pinfunction "2_2") (pintype "passive"))
      (node (ref "R9") (pin "2") (pinfunction "2_2") (pintype "passive"))
      (node (ref "U1") (pin "24") (pinfunction "USB_D+/RTC_GPIO20/GPIO20/U1CTS/ADC2_CH9/CLK_OUT1_24") (pintype "passive"))
    )
    (net (code "20") (name "/FTDI_RESET") (class "Default")
      (node (ref "C10") (pin "2") (pinfunction "2_2") (pintype "passive"))
      (node (ref "R17") (pin "2") (pinfunction "2_2") (pintype "passive"))
      (node (ref "U2") (pin "11") (pinfunction "~{RESET}_11") (pintype "passive"))
    )
    (net (code "21") (name "/FTDI_USB_N") (class "Default")
      (node (ref "R15") (pin "2") (pinfunction "2_2") (pintype "passive"))
      (node (ref "U2") (pin "9") (pinfunction "USBDM_9") (pintype "passive"))
    )
    (net (code "22") (name "/FTDI_USB_P") (class "Default")
      (node (ref "R16") (pin "2") (pinfunction "2_2") (pintype "passive"))
      (node (ref "U2") (pin "8") (pinfunction "USBDP_8") (pintype "passive"))
    )
    (net (code "23") (name "/GPIO0") (class "Default")
      (node (ref "R2") (pin "2") (pinfunction "2_2") (pintype "passive"))
      (node (ref "R5") (pin "2") (pinfunction "2_2") (pintype "passive"))
      (node (ref "U1") (pin "4") (pinfunction "GPIO0/RTC_GPIO0_4") (pintype "passive"))
    )
    (net (code "24") (name "/GPIO1") (class "Default")
      (node (ref "J1") (pin "4") (pinfunction "4_4") (pintype "passive"))
      (node (ref "U1") (pin "5") (pinfunction "GPIO1/RTC_GPIO1/TOUCH1/ADC1_CH0_5") (pintype "passive"))
    )
    (net (code "25") (name "/GPIO2") (class "Default")
      (node (ref "J1") (pin "5") (pinfunction "5_5") (pintype "passive"))
      (node (ref "LED2") (pin "1") (pinfunction "1_1") (pintype "passive"))
      (node (ref "U1") (pin "6") (pinfunction "GPIO2/RTC_GPIO2/TOUCH2/ADC1_CH1_6") (pintype "passive"))
    )
    (net (code "26") (name "/GPIO3") (class "Default")
      (node (ref "J1") (pin "6") (pinfunction "6_6") (pintype "passive"))
      (node (ref "U1") (pin "7") (pinfunction "GPIO3/RTC_GPIO3/TOUCH3/ADC1_CH2_7") (pintype "passive"))
    )
    (net (code "27") (name "/GPIO4") (class "Default")
      (node (ref "J1") (pin "7") (pinfunction "7_7") (pintype "passive"))
      (node (ref "U1") (pin "8") (pinfunction "GPIO4/RTC_GPIO4/TOUCH4/ADC1_CH3_8") (pintype "passive"))
    )
    (net (code "28") (name "/GPIO5") (class "Default")
      (node (ref "J1") (pin "8") (pinfunction "8_8") (pintype "passive"))
      (node (ref "U1") (pin "9") (pinfunction "GPIO5/RTC_GPIO5/TOUCH5/ADC1_CH4_9") (pintype "passive"))
    )
    (net (code "29") (name "/GPIO6") (class "Default")
      (node (ref "J1") (pin "9") (pinfunction "9_9") (pintype "passive"))
      (node (ref "U1") (pin "10") (pinfunction "GPIO6/RTC_GPIO6/TOUCH6/ADC1_CH5_10") (pintype "passive"))
    )
    (net (code "30") (name "/GPIO7") (class "Default")
      (node (ref "J1") (pin "10") (pinfunction "10_10") (pintype "passive"))
      (node (ref "U1") (pin "11") (pinfunction "GPIO7/RTC_GPIO7/TOUCH7/ADC1_CH6_11") (pintype "passive"))
    )
    (net (code "31") (name "/GPIO8") (class "Default")
      (node (ref "J1") (pin "11") (pinfunction "11_11") (pintype "passive"))
      (node (ref "U1") (pin "12") (pinfunction "GPIO8/RTC_GPIO8/TOUCH8/ADC1_CH7/SUBSPICS1_12") (pintype "passive"))
    )
    (net (code "32") (name "/GPIO9") (class "Default")
      (node (ref "J1") (pin "12") (pinfunction "12_12") (pintype "passive"))
      (node (ref "U1") (pin "13") (pinfunction "GPIO9/RTC_GPIO9/TOUCH9/ADC1_CH8/FSPIHD/SUBSPIHD_13") (pintype "passive"))
    )
    (net (code "33") (name "/GPIO10") (class "Default")
      (node (ref "J1") (pin "13") (pinfunction "13_13") (pintype "passive"))
      (node (ref "U1") (pin "14") (pinfunction "GPIO10/RTC_GPIO10/TOUCH10/ADC1_CH9/FSPICS0/FSPIIO4/SUBSPICS0_14") (pintype "passive"))
    )
    (net (code "34") (name "/GPIO11") (class "Default")
      (node (ref "J1") (pin "14") (pinfunction "14_14") (pintype "passive"))
      (node (ref "U1") (pin "15") (pinfunction "GPIO11/RTC_GPIO11/TOUCH11/ADC2_CH0/FSPID/FSPIIO5/SUBSPID_15") (pintype "passive"))
    )
    (net (code "35") (name "/GPIO12") (class "Default")
      (node (ref "J1") (pin "15") (pinfunction "15_15") (pintype "passive"))
      (node (ref "U1") (pin "16") (pinfunction "GPIO12/RTC_GPIO12/TOUCH12/ADC2_CH1/FSPICLK/FSPIIO6/SUBSPICLK_16") (pintype "passive"))
    )
    (net (code "36") (name "/GPIO13") (class "Default")
      (node (ref "J1") (pin "16") (pinfunction "16_16") (pintype "passive"))
      (node (ref "U1") (pin "17") (pinfunction "GPIO13/RTC_GPIO13/TOUCH13/ADC2_CH2/FSPIQ/FSPIIO7/SUBSPIQ_17") (pintype "passive"))
    )
    (net (code "37") (name "/GPIO14") (class "Default")
      (node (ref "J1") (pin "17") (pinfunction "17_17") (pintype "passive"))
      (node (ref "U1") (pin "18") (pinfunction "GPIO14/RTC_GPIO14/TOUCH14/ADC2_CH3/FSPIWP/FSPIDQS/SUBSPIWP_18") (pintype "passive"))
    )
    (net (code "38") (name "/GPIO15") (class "Default")
      (node (ref "J1") (pin "18") (pinfunction "18_18") (pintype "passive"))
      (node (ref "U1") (pin "19") (pinfunction "GPIO15/RTC_GPIO15/U0RTS/ADC2_CH4/XTAL_32K_P_19") (pintype "passive"))
    )
    (net (code "39") (name "/GPIO16") (class "Default")
      (node (ref "J1") (pin "19") (pinfunction "19_19") (pintype "passive"))
      (node (ref "U1") (pin "20") (pinfunction "GPIO16/RTC_GPIO16/U0CTS/ADC2_CH5/XTAL_32K_N_20") (pintype "passive"))
    )
    (net (code "40") (name "/GPIO17") (class "Default")
      (node (ref "J1") (pin "20") (pinfunction "20_20") (pintype "passive"))
      (node (ref "U1") (pin "21") (pinfunction "GPIO17/RTC_GPIO17/U1TXD/ADC2_CH6_21") (pintype "passive"))
    )
    (net (code "41") (name "/GPIO18") (class "Default")
      (node (ref "J1") (pin "21") (pinfunction "21_21") (pintype "passive"))
      (node (ref "U1") (pin "22") (pinfunction "GPIO18/RTC_GPIO18/U1RXD/ADC2_CH7/CLK_OUT3_22") (pintype "passive"))
    )
    (net (code "42") (name "/GPIO21") (class "Default")
      (node (ref "J2") (pin "19") (pinfunction "19_19") (pintype "passive"))
      (node (ref "U1") (pin "25") (pinfunction "GPIO21/RTC_GPIO21_25") (pintype "passive"))
    )
    (net (code "43") (name "/GPIO26") (class "Default")
      (node (ref "J2") (pin "18") (pinfunction "18_18") (pintype "passive"))
      (node (ref "U1") (pin "26") (pinfunction "GPIO26/SPICS1_26") (pintype "passive"))
    )
    (net (code "44") (name "/GPIO33") (class "Default")
      (node (ref "J2") (pin "17") (pinfunction "17_17") (pintype "passive"))
      (node (ref "U1") (pin "28") (pinfunction "GPIO33/SPIIO4/FSPIHD/SUBSPIHD_28") (pintype "passive"))
    )
    (net (code "45") (name "/GPIO34") (class "Default")
      (node (ref "J2") (pin "16") (pinfunction "16_16") (pintype "passive"))
      (node (ref "U1") (pin "29") (pinfunction "GPIO34/SPIIO5/FSPICS0/SUBSPICS0_29") (pintype "passive"))
    )
    (net (code "46") (name "/GPIO35") (class "Default")
      (node (ref "J2") (pin "15") (pinfunction "15_15") (pintype "passive"))
      (node (ref "U1") (pin "31") (pinfunction "GPIO35/SPIIO6/FSPID/SUBSPID_31") (pintype "passive"))
    )
    (net (code "47") (name "/GPIO36") (class "Default")
      (node (ref "J2") (pin "14") (pinfunction "14_14") (pintype "passive"))
      (node (ref "U1") (pin "32") (pinfunction "GPIO36/SPIIO7/FSPICLK/SUBSPICLK_32") (pintype "passive"))
    )
    (net (code "48") (name "/GPIO37") (class "Default")
      (node (ref "J2") (pin "13") (pinfunction "13_13") (pintype "passive"))
      (node (ref "U1") (pin "33") (pinfunction "GPIO37/SPIDQS/FSPIQ/SUBSPIQ_33") (pintype "passive"))
    )
    (net (code "49") (name "/GPIO38") (class "Default")
      (node (ref "J2") (pin "12") (pinfunction "12_12") (pintype "passive"))
      (node (ref "U1") (pin "34") (pinfunction "GPIO38/FSPIWP/SUBSPIWP_34") (pintype "passive"))
    )
    (net (code "50") (name "/GPIO39") (class "Default")
      (node (ref "J2") (pin "11") (pinfunction "11_11") (pintype "passive"))
      (node (ref "U1") (pin "35") (pinfunction "MTCK/GPIO39/CLK_OUT3/SUBSPICS1_35") (pintype "passive"))
    )
    (net (code "51") (name "/GPIO40") (class "Default")
      (node (ref "J2") (pin "10") (pinfunction "10_10") (pintype "passive"))
      (node (ref "U1") (pin "36") (pinfunction "MTDO/GPIO40/CLK_OUT2_36") (pintype "passive"))
    )
    (net (code "52") (name "/GPIO41") (class "Default")
      (node (ref "J2") (pin "9") (pinfunction "9_9") (pintype "passive"))
      (node (ref "U1") (pin "37") (pinfunction "MTDI/GPIO41/CLK_OUT1_37") (pintype "passive"))
    )
    (net (code "53") (name "/GPIO42") (class "Default")
      (node (ref "J2") (pin "8") (pinfunction "8_8") (pintype "passive"))
      (node (ref "U1") (pin "38") (pinfunction "MTMS/GPIO42_38") (pintype "passive"))
    )
    (net (code "54") (name "/GPIO45") (class "Default")
      (node (ref "J2") (pin "5") (pinfunction "5_5") (pintype "passive"))
      (node (ref "U1") (pin "41") (pinfunction "GPIO45_41") (pintype "passive"))
    )
    (net (code "55") (name "/GPIO46") (class "Default")
      (node (ref "J2") (pin "4") (pinfunction "4_4") (pintype "passive"))
      (node (ref "U1") (pin "44") (pinfunction "GPIO46_44") (pintype "passive"))
    )
    (net (code "56") (name "/GPIO47") (class "Default")
      (node (ref "J2") (pin "23") (pinfunction "23_23") (pintype "passive"))
      (node (ref "U1") (pin "27") (pinfunction "GPIO47/SPICLK_P_DIFF/SUBSPICLK_P_DIFF_27") (pintype "passive"))
    )
    (net (code "57") (name "/GPIO48") (class "Default")
      (node (ref "J2") (pin "22") (pinfunction "22_22") (pintype "passive"))
      (node (ref "U1") (pin "30") (pinfunction "GPIO48/SPICLK_N_DIFF/SUBSPICLK_N_DIFF_30") (pintype "passive"))
    )
    (net (code "58") (name "/RTS_FTDI") (class "Default")
      (node (ref "Q1") (pin "2") (pinfunction "E_2") (pintype "passive"))
      (node (ref "R24") (pin "1") (pinfunction "1_1") (pintype "passive"))
      (node (ref "U2") (pin "19") (pinfunction "~{RTS}_19") (pintype "passive"))
    )
    (net (code "59") (name "/RXD_FTDI") (class "Default")
      (node (ref "R4") (pin "2") (pinfunction "2_2") (pintype "passive"))
      (node (ref "U2") (pin "1") (pinfunction "RXD_1") (pintype "passive"))
    )
    (net (code "60") (name "/TXD_FTDI") (class "Default")
      (node (ref "R3") (pin "2") (pinfunction "2_2") (pintype "passive"))
      (node (ref "U2") (pin "17") (pinfunction "TXD_17") (pintype "passive"))
    )
    (net (code "61") (name "/U0RXD") (class "Default")
      (node (ref "J2") (pin "6") (pinfunction "6_6") (pintype "passive"))
      (node (ref "R3") (pin "1") (pinfunction "1_1") (pintype "passive"))
      (node (ref "U1") (pin "40") (pinfunction "U0RXD/GPIO44/CLK_OUT2_40") (pintype "passive"))
    )
    (net (code "62") (name "/U0TXD") (class "Default")
      (node (ref "J2") (pin "7") (pinfunction "7_7") (pintype "passive"))
      (node (ref "R4") (pin "1") (pinfunction "1_1") (pintype "passive"))
      (node (ref "U1") (pin "39") (pinfunction "U0TXD/GPIO43/CLK_OUT1_39") (pintype "passive"))
    )
    (net (code "63") (name "/VBUS_SENSE") (class "Default")
      (node (ref "R21") (pin "1") (pinfunction "1_1") (pintype "passive"))
      (node (ref "R22") (pin "2") (pinfunction "2_2") (pintype "passive"))
      (node (ref "U2") (pin "16") (pinfunction "CBUS3_16") (pintype "passive"))
    )
    (net (code "64") (name "GND") (class "Default")
      (node (ref "C1") (pin "1") (pinfunction "1_1") (pintype "passive"))
      (node (ref "C10") (pin "1") (pinfunction "1_1") (pintype "passive"))
      (node (ref "C11") (pin "1") (pinfunction "1_1") (pintype "passive"))
      (node (ref "C12") (pin "1") (pinfunction "1_1") (pintype "passive"))
      (node (ref "C13") (pin "1") (pinfunction "1_1") (pintype "passive"))
      (node (ref "C14") (pin "1") (pinfunction "1_1") (pintype "passive"))
      (node (ref "C15") (pin "1") (pinfunction "1_1") (pintype "passive"))
      (node (ref "C16") (pin "1") (pinfunction "1_1") (pintype "passive"))
      (node (ref "C17") (pin "1") (pinfunction "1_1") (pintype "passive"))
      (node (ref "C2") (pin "1") (pinfunction "1_1") (pintype "passive"))
      (node (ref "C3") (pin "1") (pinfunction "1_1") (pintype "passive"))
      (node (ref "C4") (pin "1") (pinfunction "1_1") (pintype "passive"))
      (node (ref "C5") (pin "1") (pinfunction "1_1") (pintype "passive"))
      (node (ref "C6") (pin "1") (pinfunction "1_1") (pintype "passive"))
      (node (ref "C7") (pin "1") (pinfunction "1_1") (pintype "passive"))
      (node (ref "C8") (pin "1") (pinfunction "1_1") (pintype "passive"))
      (node (ref "C9") (pin "1") (pinfunction "1_1") (pintype "passive"))
      (node (ref "D1") (pin "1") (pinfunction "1_1") (pintype "passive"))
      (node (ref "D2") (pin "1") (pinfunction "1_1") (pintype "passive"))
      (node (ref "D3") (pin "1") (pinfunction "1_1") (pintype "passive"))
      (node (ref "D4") (pin "1") (pinfunction "1_1") (pintype "passive"))
      (node (ref "D5") (pin "1") (pinfunction "1_1") (pintype "passive"))
      (node (ref "D6") (pin "1") (pinfunction "1_1") (pintype "passive"))
      (node (ref "J1") (pin "1") (pinfunction "1_1") (pintype "passive"))
      (node (ref "J1") (pin "23") (pinfunction "23_23") (pintype "passive"))
      (node (ref "J2") (pin "2") (pinfunction "2_2") (pintype "passive"))
      (node (ref "J2") (pin "24") (pinfunction "24_24") (pintype "passive"))
      (node (ref "J3") (pin "A1B12") (pinfunction "GND_A1B12_A1B12") (pintype "passive"))
      (node (ref "J3") (pin "B1A12") (pinfunction "GND_B1A12_B1A12") (pintype "passive"))
      (node (ref "J3") (pin "S1") (pinfunction "SHIELD_1_S1") (pintype "passive"))
      (node (ref "J3") (pin "S2") (pinfunction "SHIELD_2_S2") (pintype "passive"))
      (node (ref "J3") (pin "S3") (pinfunction "SHIELD_3_S3") (pintype "passive"))
      (node (ref "J3") (pin "S4") (pinfunction "SHIELD_4_S4") (pintype "passive"))
      (node (ref "J4") (pin "A1B12") (pinfunction "GND_A1B12_A1B12") (pintype "passive"))
      (node (ref "J4") (pin "B1A12") (pinfunction "GND_B1A12_B1A12") (pintype "passive"))
      (node (ref "J4") (pin "S1") (pinfunction "SHIELD_1_S1") (pintype "passive"))
      (node (ref "J4") (pin "S2") (pinfunction "SHIELD_2_S2") (pintype "passive"))
      (node (ref "J4") (pin "S3") (pinfunction "SHIELD_3_S3") (pintype "passive"))
      (node (ref "J4") (pin "S4") (pinfunction "SHIELD_4_S4") (pintype "passive"))
      (node (ref "LED1") (pin "1") (pinfunction "1_1") (pintype "passive"))
      (node (ref "R18") (pin "1") (pinfunction "1_1") (pintype "passive"))
      (node (ref "R19") (pin "1") (pinfunction "1_1") (pintype "passive"))
      (node (ref "R20") (pin "2") (pinfunction "2_2") (pintype "passive"))
      (node (ref "R22") (pin "1") (pinfunction "1_1") (pintype "passive"))
      (node (ref "R6") (pin "1") (pinfunction "1_1") (pintype "passive"))
      (node (ref "R7") (pin "1") (pinfunction "1_1") (pintype "passive"))
      (node (ref "SW1") (pin "3") (pinfunction "3_3") (pintype "passive"))
      (node (ref "SW1") (pin "4") (pinfunction "4_4") (pintype "passive"))
      (node (ref "SW2") (pin "3") (pinfunction "3_3") (pintype "passive"))
      (node (ref "SW2") (pin "4") (pinfunction "4_4") (pintype "passive"))
      (node (ref "U1") (pin "1") (pinfunction "GND_01_1") (pintype "passive"))
      (node (ref "U1") (pin "2") (pinfunction "GND_02_2") (pintype "passive"))
      (node (ref "U1") (pin "42") (pinfunction "GND_42") (pintype "passive"))
      (node (ref "U1") (pin "43") (pinfunction "GND_43") (pintype "passive"))
      (node (ref "U1") (pin "46") (pinfunction "GND_46_46") (pintype "passive"))
      (node (ref "U1") (pin "47") (pinfunction "GND_47_47") (pintype "passive"))
      (node (ref "U1") (pin "48") (pinfunction "GND_48_48") (pintype "passive"))
      (node (ref "U1") (pin "49") (pinfunction "GND_49_49") (pintype "passive"))
      (node (ref "U1") (pin "50") (pinfunction "GND_50_50") (pintype "passive"))
      (node (ref "U1") (pin "51") (pinfunction "GND_51_51") (pintype "passive"))
      (node (ref "U1") (pin "52") (pinfunction "GND_52_52") (pintype "passive"))
      (node (ref "U1") (pin "53") (pinfunction "GND_53_53") (pintype "passive"))
      (node (ref "U1") (pin "54") (pinfunction "GND_54_54") (pintype "passive"))
      (node (ref "U1") (pin "55") (pinfunction "GND_55_55") (pintype "passive"))
      (node (ref "U1") (pin "56") (pinfunction "GND_56_56") (pintype "passive"))
      (node (ref "U1") (pin "57") (pinfunction "GND_57_57") (pintype "passive"))
      (node (ref "U1") (pin "58") (pinfunction "GND_58_58") (pintype "passive"))
      (node (ref "U1") (pin "59") (pinfunction "GND_59_59") (pintype "passive"))
      (node (ref "U1") (pin "60") (pinfunction "GND_60_60") (pintype "passive"))
      (node (ref "U1") (pin "61") (pinfunction "GND_61_61") (pintype "passive"))
      (node (ref "U1") (pin "62") (pinfunction "GND_62_62") (pintype "passive"))
      (node (ref "U1") (pin "63") (pinfunction "GND_63_63") (pintype "passive"))
      (node (ref "U1") (pin "64") (pinfunction "GND_64_64") (pintype "passive"))
      (node (ref "U1") (pin "65") (pinfunction "GND_65_65") (pintype "passive"))
      (node (ref "U1") (pin "66") (pinfunction "GND_66_66") (pintype "passive"))
      (node (ref "U1") (pin "67") (pinfunction "GND_67_67") (pintype "passive"))
      (node (ref "U1") (pin "68") (pinfunction "GND_68_68") (pintype "passive"))
      (node (ref "U1") (pin "69") (pinfunction "GND_69_69") (pintype "passive"))
      (node (ref "U1") (pin "70") (pinfunction "GND_70_70") (pintype "passive"))
      (node (ref "U1") (pin "71") (pinfunction "GND_71_71") (pintype "passive"))
      (node (ref "U1") (pin "72") (pinfunction "GND_72_72") (pintype "passive"))
      (node (ref "U1") (pin "73") (pinfunction "GND_73_73") (pintype "passive"))
      (node (ref "U2") (pin "13") (pinfunction "GND_13") (pintype "passive"))
      (node (ref "U2") (pin "21") (pinfunction "GND_21") (pintype "passive"))
      (node (ref "U2") (pin "3") (pinfunction "GND_3") (pintype "passive"))
      (node (ref "U3") (pin "2") (pinfunction "GND_2") (pintype "power_in"))
      (node (ref "U3") (pin "4") (pinfunction "GND_4") (pintype "power_in"))
    )
    (net (code "65") (name "Net-(J3-CC1)") (class "Default")
      (node (ref "J3") (pin "A5") (pinfunction "CC1_A5") (pintype "passive"))
      (node (ref "R6") (pin "2") (pinfunction "2_2") (pintype "passive"))
    )
    (net (code "66") (name "Net-(J3-CC2)") (class "Default")
      (node (ref "J3") (pin "B5") (pinfunction "CC2_B5") (pintype "passive"))
      (node (ref "R7") (pin "2") (pinfunction "2_2") (pintype "passive"))
    )
    (net (code "67") (name "Net-(J4-CC1)") (class "Default")
      (node (ref "J4") (pin "A5") (pinfunction "CC1_A5") (pintype "passive"))
      (node (ref "R18") (pin "2") (pinfunction "2_2") (pintype "passive"))
    )
    (net (code "68") (name "Net-(J4-CC2)") (class "Default")
      (node (ref "J4") (pin "B5") (pinfunction "CC2_B5") (pintype "passive"))
      (node (ref "R19") (pin "2") (pinfunction "2_2") (pintype "passive"))
    )
    (net (code "69") (name "Net-(LED1-Pad2)") (class "Default")
      (node (ref "LED1") (pin "2") (pinfunction "2_2") (pintype "passive"))
      (node (ref "R25") (pin "1") (pinfunction "1_1") (pintype "passive"))
    )
    (net (code "70") (name "Net-(LED2-Pad2)") (class "Default")
      (node (ref "LED2") (pin "2") (pinfunction "2_2") (pintype "passive"))
      (node (ref "R26") (pin "1") (pinfunction "1_1") (pintype "passive"))
    )
    (net (code "71") (name "Net-(Q1-B)") (class "Default")
      (node (ref "Q1") (pin "1") (pinfunction "B_1") (pintype "passive"))
      (node (ref "R23") (pin "2") (pinfunction "2_2") (pintype "passive"))
    )
    (net (code "72") (name "Net-(Q2-B)") (class "Default")
      (node (ref "Q2") (pin "1") (pinfunction "B_1") (pintype "passive"))
      (node (ref "R24") (pin "2") (pinfunction "2_2") (pintype "passive"))
    )
    (net (code "73") (name "Net-(U2-CBUS0)") (class "Default")
      (node (ref "R20") (pin "1") (pinfunction "1_1") (pintype "passive"))
      (node (ref "U2") (pin "15") (pinfunction "CBUS0_15") (pintype "passive"))
    )
    (net (code "74") (name "unconnected-(J1-Pad24)") (class "Default")
      (node (ref "J1") (pin "24") (pinfunction "24_24") (pintype "passive+no_connect"))
    )
    (net (code "75") (name "unconnected-(J3-SBU1-PadA8)") (class "Default")
      (node (ref "J3") (pin "A8") (pinfunction "SBU1_A8") (pintype "passive+no_connect"))
    )
    (net (code "76") (name "unconnected-(J3-SBU2-PadB8)") (class "Default")
      (node (ref "J3") (pin "B8") (pinfunction "SBU2_B8") (pintype "passive+no_connect"))
    )
    (net (code "77") (name "unconnected-(J4-SBU1-PadA8)") (class "Default")
      (node (ref "J4") (pin "A8") (pinfunction "SBU1_A8") (pintype "passive+no_connect"))
    )
    (net (code "78") (name "unconnected-(J4-SBU2-PadB8)") (class "Default")
      (node (ref "J4") (pin "B8") (pinfunction "SBU2_B8") (pintype "passive+no_connect"))
    )
    (net (code "79") (name "unconnected-(U2-CBUS1-Pad14)") (class "Default")
      (node (ref "U2") (pin "14") (pinfunction "CBUS1_14") (pintype "passive+no_connect"))
    )
    (net (code "80") (name "unconnected-(U2-CBUS2-Pad7)") (class "Default")
      (node (ref "U2") (pin "7") (pinfunction "CBUS2_7") (pintype "passive+no_connect"))
    )
    (net (code "81") (name "unconnected-(U2-~{CTS}-Pad6)") (class "Default")
      (node (ref "U2") (pin "6") (pinfunction "~{CTS}_6") (pintype "passive"))
    )
    (net (code "82") (name "unconnected-(U2-~{DCD}-Pad5)") (class "Default")
      (node (ref "U2") (pin "5") (pinfunction "~{DCD}_5") (pintype "passive+no_connect"))
    )
    (net (code "83") (name "unconnected-(U2-~{DSR}-Pad4)") (class "Default")
      (node (ref "U2") (pin "4") (pinfunction "~{DSR}_4") (pintype "passive+no_connect"))
    )
    (net (code "84") (name "unconnected-(U2-~{RI}-Pad2)") (class "Default")
      (node (ref "U2") (pin "2") (pinfunction "~{RI}_2") (pintype "passive+no_connect"))
    )
  )
)
